# ELM327-based_OBD-II_interface.net
KiCad netlist of a schematic drawn in EAGLE
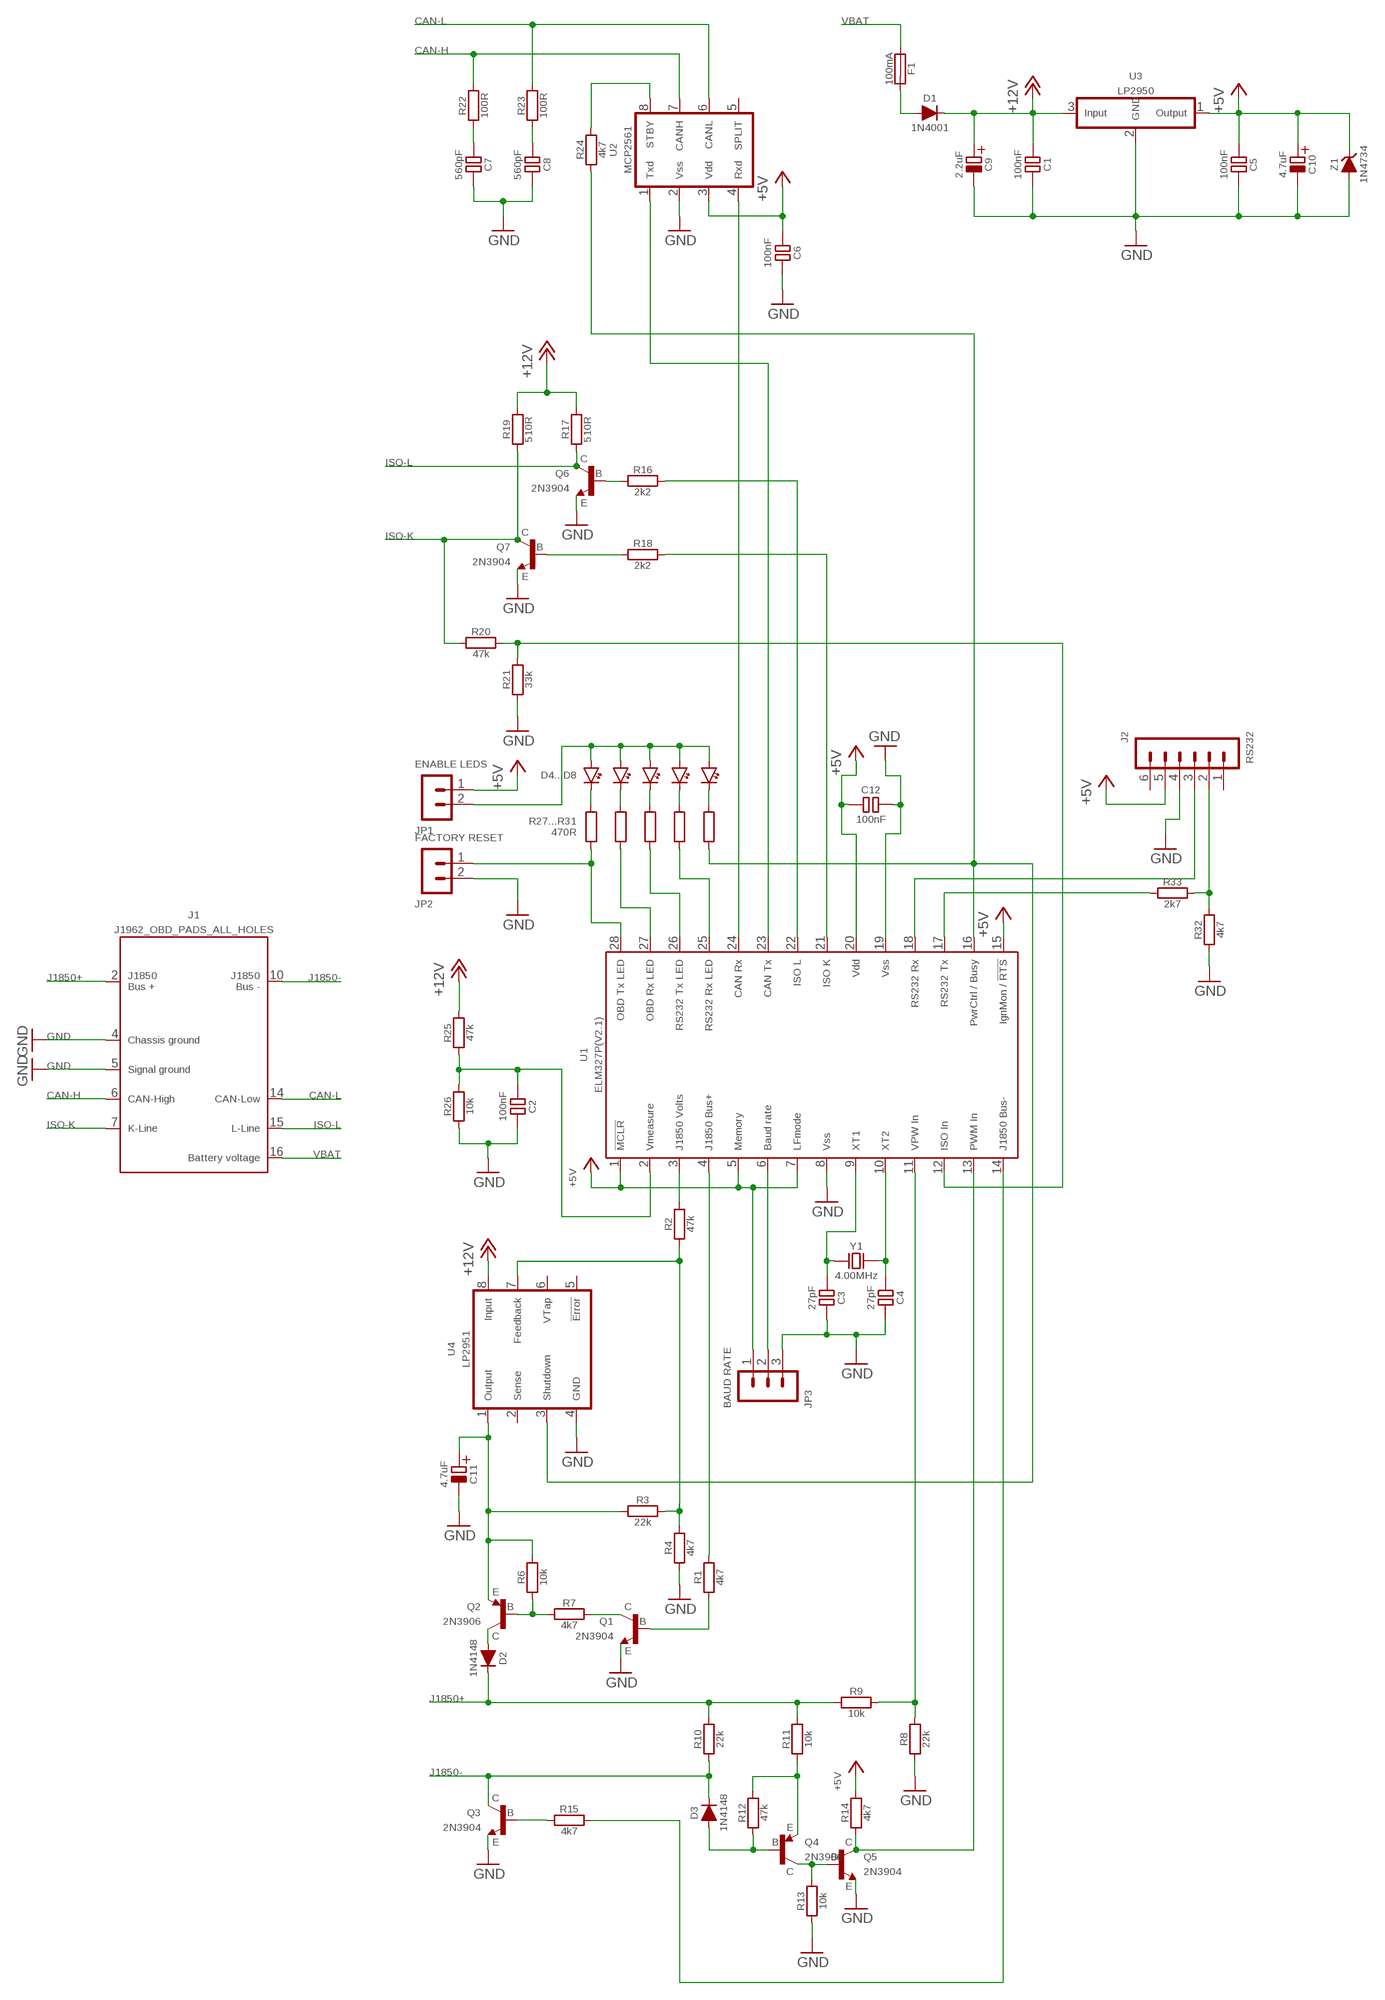
[diagram p0: schematic, sheet 1]

(export (version "E")
  (design (tool "Eeschema 10.0.6"))
  (components
    (comp (ref "C1")
      (value "100nF")
      (footprint "eagle-import:MLCC-5.08")
      (libsource (lib "eagle-import") (part "C(MLCC-5.08)"))
    )
    (comp (ref "C2")
      (value "100nF")
      (footprint "eagle-import:MLCC-5.08")
      (libsource (lib "eagle-import") (part "C(MLCC-5.08)"))
    )
    (comp (ref "C3")
      (value "27pF")
      (footprint "eagle-import:MLCC-5.08")
      (libsource (lib "eagle-import") (part "C(MLCC-5.08)"))
    )
    (comp (ref "C4")
      (value "27pF")
      (footprint "eagle-import:MLCC-5.08")
      (libsource (lib "eagle-import") (part "C(MLCC-5.08)"))
    )
    (comp (ref "C5")
      (value "100nF")
      (footprint "eagle-import:MLCC-5.08")
      (libsource (lib "eagle-import") (part "C(MLCC-5.08)"))
    )
    (comp (ref "C6")
      (value "100nF")
      (footprint "eagle-import:MLCC-5.08")
      (libsource (lib "eagle-import") (part "C(MLCC-5.08)"))
    )
    (comp (ref "C7")
      (value "560pF")
      (footprint "eagle-import:MLCC-5.08")
      (libsource (lib "eagle-import") (part "C(MLCC-5.08)"))
    )
    (comp (ref "C8")
      (value "560pF")
      (footprint "eagle-import:MLCC-5.08")
      (libsource (lib "eagle-import") (part "C(MLCC-5.08)"))
    )
    (comp (ref "C9")
      (value "2.2uF")
      (footprint "eagle-import:E2-5")
      (libsource (lib "eagle-import") (part "CPOL(E2-5)"))
    )
    (comp (ref "C10")
      (value "4.7uF")
      (footprint "eagle-import:TANTALUM-5.08")
      (libsource (lib "eagle-import") (part "CPOL(TANTALUM-5.08)"))
    )
    (comp (ref "C11")
      (value "4.7uF")
      (footprint "eagle-import:TANTALUM-5.08")
      (libsource (lib "eagle-import") (part "CPOL(TANTALUM-5.08)"))
    )
    (comp (ref "C12")
      (value "100nF")
      (footprint "eagle-import:MLCC-5.08")
      (libsource (lib "eagle-import") (part "C(MLCC-5.08)"))
    )
    (comp (ref "D1")
      (value "1N4001")
      (footprint "eagle-import:DO-41")
      (libsource (lib "eagle-import") (part "DIODE(?)DO-41"))
    )
    (comp (ref "D2")
      (value "1N4148")
      (footprint "eagle-import:DO-35")
      (libsource (lib "eagle-import") (part "DIODE(?)DO-35"))
    )
    (comp (ref "D3")
      (value "1N4148")
      (footprint "eagle-import:DO-35")
      (libsource (lib "eagle-import") (part "DIODE(?)DO-35"))
    )
    (comp (ref "D4")
      (value "OBD Tx")
      (footprint "eagle-import:LED_5MM")
      (libsource (lib "eagle-import") (part "LED(?)5MM"))
    )
    (comp (ref "D5")
      (value "OBD Rx")
      (footprint "eagle-import:LED_5MM")
      (libsource (lib "eagle-import") (part "LED(?)5MM"))
    )
    (comp (ref "D6")
      (value "RS232 Tx")
      (footprint "eagle-import:LED_5MM")
      (libsource (lib "eagle-import") (part "LED(?)5MM"))
    )
    (comp (ref "D7")
      (value "RS232 Rx")
      (footprint "eagle-import:LED_5MM")
      (libsource (lib "eagle-import") (part "LED(?)5MM"))
    )
    (comp (ref "D8")
      (value "ON")
      (footprint "eagle-import:LED_5MM")
      (libsource (lib "eagle-import") (part "LED(?)5MM"))
    )
    (comp (ref "F1")
      (value "100mA")
      (footprint "eagle-import:FUSE")
      (libsource (lib "eagle-import") (part "FUSE"))
    )
    (comp (ref "J1")
      (value "J1962_OBD_PADS_ALL_HOLES")
      (footprint "eagle-import:J1962_OBD_PADS_ALL_HOLES")
      (libsource (lib "eagle-import") (part "J1962_OBD_PADS_?ALL_HOLES"))
    )
    (comp (ref "J2")
      (value "RS232")
      (footprint "eagle-import:HEADER_1X6")
      (libsource (lib "eagle-import") (part "HEADER_1X6"))
    )
    (comp (ref "JP1")
      (value "ENABLE LEDS")
      (footprint "eagle-import:HEADER_1X2")
      (libsource (lib "eagle-import") (part "HEADER_1X2"))
    )
    (comp (ref "JP2")
      (value "FACTORY RESET")
      (footprint "eagle-import:HEADER_1X2")
      (libsource (lib "eagle-import") (part "HEADER_1X2"))
    )
    (comp (ref "JP3")
      (value "BAUD RATE")
      (footprint "eagle-import:HEADER_1X3")
      (libsource (lib "eagle-import") (part "HEADER_1X3"))
    )
    (comp (ref "Q1")
      (value "2N3904")
      (footprint "eagle-import:TO-92")
      (libsource (lib "eagle-import") (part "NPN(TO-92)"))
    )
    (comp (ref "Q2")
      (value "2N3906")
      (footprint "eagle-import:TO-92")
      (libsource (lib "eagle-import") (part "PNP(TO-92)"))
    )
    (comp (ref "Q3")
      (value "2N3904")
      (footprint "eagle-import:TO-92")
      (libsource (lib "eagle-import") (part "NPN(TO-92)"))
    )
    (comp (ref "Q4")
      (value "2N3906")
      (footprint "eagle-import:TO-92")
      (libsource (lib "eagle-import") (part "PNP(TO-92)"))
    )
    (comp (ref "Q5")
      (value "2N3904")
      (footprint "eagle-import:TO-92")
      (libsource (lib "eagle-import") (part "NPN(TO-92)"))
    )
    (comp (ref "Q6")
      (value "2N3904")
      (footprint "eagle-import:TO-92")
      (libsource (lib "eagle-import") (part "NPN(TO-92)"))
    )
    (comp (ref "Q7")
      (value "2N3904")
      (footprint "eagle-import:TO-92")
      (libsource (lib "eagle-import") (part "NPN(TO-92)"))
    )
    (comp (ref "R1")
      (value "4k7")
      (footprint "eagle-import:MF12-1_8W")
      (libsource (lib "eagle-import") (part "R-EU-?MF12-1/8W"))
    )
    (comp (ref "R2")
      (value "47k")
      (footprint "eagle-import:MF12-1_8W")
      (libsource (lib "eagle-import") (part "R-EU-?MF12-1/8W"))
    )
    (comp (ref "R3")
      (value "22k")
      (footprint "eagle-import:MF12-1_8W")
      (libsource (lib "eagle-import") (part "R-EU-?MF12-1/8W"))
    )
    (comp (ref "R4")
      (value "4k7")
      (footprint "eagle-import:MF12-1_8W")
      (libsource (lib "eagle-import") (part "R-EU-?MF12-1/8W"))
    )
    (comp (ref "R6")
      (value "10k")
      (footprint "eagle-import:MF12-1_8W")
      (libsource (lib "eagle-import") (part "R-EU-?MF12-1/8W"))
    )
    (comp (ref "R7")
      (value "4k7")
      (footprint "eagle-import:MF12-1_8W")
      (libsource (lib "eagle-import") (part "R-EU-?MF12-1/8W"))
    )
    (comp (ref "R8")
      (value "22k")
      (footprint "eagle-import:MF12-1_8W")
      (libsource (lib "eagle-import") (part "R-EU-?MF12-1/8W"))
    )
    (comp (ref "R9")
      (value "10k")
      (footprint "eagle-import:MF12-1_8W")
      (libsource (lib "eagle-import") (part "R-EU-?MF12-1/8W"))
    )
    (comp (ref "R10")
      (value "22k")
      (footprint "eagle-import:MF12-1_8W")
      (libsource (lib "eagle-import") (part "R-EU-?MF12-1/8W"))
    )
    (comp (ref "R11")
      (value "10k")
      (footprint "eagle-import:MF12-1_8W")
      (libsource (lib "eagle-import") (part "R-EU-?MF12-1/8W"))
    )
    (comp (ref "R12")
      (value "47k")
      (footprint "eagle-import:MF12-1_8W")
      (libsource (lib "eagle-import") (part "R-EU-?MF12-1/8W"))
    )
    (comp (ref "R13")
      (value "10k")
      (footprint "eagle-import:MF12-1_8W")
      (libsource (lib "eagle-import") (part "R-EU-?MF12-1/8W"))
    )
    (comp (ref "R14")
      (value "4k7")
      (footprint "eagle-import:MF12-1_8W")
      (libsource (lib "eagle-import") (part "R-EU-?MF12-1/8W"))
    )
    (comp (ref "R15")
      (value "4k7")
      (footprint "eagle-import:MF12-1_8W")
      (libsource (lib "eagle-import") (part "R-EU-?MF12-1/8W"))
    )
    (comp (ref "R16")
      (value "2k2")
      (footprint "eagle-import:MF12-1_8W")
      (libsource (lib "eagle-import") (part "R-EU-?MF12-1/8W"))
    )
    (comp (ref "R17")
      (value "510R")
      (footprint "eagle-import:MF50-1_2W")
      (libsource (lib "eagle-import") (part "R-EU-?MF50-1/2W"))
    )
    (comp (ref "R18")
      (value "2k2")
      (footprint "eagle-import:MF12-1_8W")
      (libsource (lib "eagle-import") (part "R-EU-?MF12-1/8W"))
    )
    (comp (ref "R19")
      (value "510R")
      (footprint "eagle-import:MF50-1_2W")
      (libsource (lib "eagle-import") (part "R-EU-?MF50-1/2W"))
    )
    (comp (ref "R20")
      (value "47k")
      (footprint "eagle-import:MF12-1_8W")
      (libsource (lib "eagle-import") (part "R-EU-?MF12-1/8W"))
    )
    (comp (ref "R21")
      (value "33k")
      (footprint "eagle-import:MF12-1_8W")
      (libsource (lib "eagle-import") (part "R-EU-?MF12-1/8W"))
    )
    (comp (ref "R22")
      (value "100R")
      (footprint "eagle-import:MF12-1_8W")
      (libsource (lib "eagle-import") (part "R-EU-?MF12-1/8W"))
    )
    (comp (ref "R23")
      (value "100R")
      (footprint "eagle-import:MF12-1_8W")
      (libsource (lib "eagle-import") (part "R-EU-?MF12-1/8W"))
    )
    (comp (ref "R24")
      (value "4k7")
      (footprint "eagle-import:MF12-1_8W")
      (libsource (lib "eagle-import") (part "R-EU-?MF12-1/8W"))
    )
    (comp (ref "R25")
      (value "47k")
      (footprint "eagle-import:MF12-1_8W")
      (libsource (lib "eagle-import") (part "R-EU-?MF12-1/8W"))
    )
    (comp (ref "R26")
      (value "10k")
      (footprint "eagle-import:MF12-1_8W")
      (libsource (lib "eagle-import") (part "R-EU-?MF12-1/8W"))
    )
    (comp (ref "R27")
      (value "470R")
      (footprint "eagle-import:MF12-1_8W")
      (libsource (lib "eagle-import") (part "R-EU-?MF12-1/8W"))
    )
    (comp (ref "R28")
      (value "470R")
      (footprint "eagle-import:MF12-1_8W")
      (libsource (lib "eagle-import") (part "R-EU-?MF12-1/8W"))
    )
    (comp (ref "R29")
      (value "470R")
      (footprint "eagle-import:MF12-1_8W")
      (libsource (lib "eagle-import") (part "R-EU-?MF12-1/8W"))
    )
    (comp (ref "R30")
      (value "470R")
      (footprint "eagle-import:MF12-1_8W")
      (libsource (lib "eagle-import") (part "R-EU-?MF12-1/8W"))
    )
    (comp (ref "R31")
      (value "470R")
      (footprint "eagle-import:MF12-1_8W")
      (libsource (lib "eagle-import") (part "R-EU-?MF12-1/8W"))
    )
    (comp (ref "R32")
      (value "4k7")
      (footprint "eagle-import:MF12-1_8W")
      (libsource (lib "eagle-import") (part "R-EU-?MF12-1/8W"))
    )
    (comp (ref "R33")
      (value "2k7")
      (footprint "eagle-import:MF12-1_8W")
      (libsource (lib "eagle-import") (part "R-EU-?MF12-1/8W"))
    )
    (comp (ref "U1")
      (value "ELM327P(V2.1)")
      (footprint "eagle-import:SPDIP(28)")
      (libsource (lib "eagle-import") (part "ELM327?(V2.1)P"))
    )
    (comp (ref "U2")
      (value "MCP2561")
      (footprint "eagle-import:PDIP")
      (libsource (lib "eagle-import") (part "MCP2561FD(?)PDIP"))
    )
    (comp (ref "U3")
      (value "LP2950")
      (footprint "eagle-import:TO-92")
      (libsource (lib "eagle-import") (part "LP2950?Z-5.0AC"))
    )
    (comp (ref "U4")
      (value "LP2951")
      (footprint "eagle-import:PDIP-8")
      (libsource (lib "eagle-import") (part "LP2951?NAC"))
    )
    (comp (ref "Y1")
      (value "4.00MHz")
      (footprint "eagle-import:HC49")
      (libsource (lib "eagle-import") (part "HUS-4.000-18-30/50/-40+85"))
    )
    (comp (ref "Z1")
      (value "1N4734")
      (footprint "eagle-import:DO-41")
      (libsource (lib "eagle-import") (part "ZENER(?)DO-41"))
    )
  )
  (nets
    (net (code "1") (name "+5V") (class "Default")
      (node (ref "C10") (pin "+") (pinfunction "+_+") (pintype "passive"))
      (node (ref "C12") (pin "+") (pinfunction "+_+") (pintype "passive"))
      (node (ref "C5") (pin "+") (pinfunction "+_+") (pintype "passive"))
      (node (ref "C6") (pin "+") (pinfunction "+_+") (pintype "passive"))
      (node (ref "J2") (pin "5") (pinfunction "5_5") (pintype "passive"))
      (node (ref "JP1") (pin "1") (pinfunction "1_1") (pintype "passive"))
      (node (ref "JP3") (pin "1") (pinfunction "1_1") (pintype "passive"))
      (node (ref "R14") (pin "2") (pinfunction "2_2") (pintype "passive"))
      (node (ref "U1") (pin "1") (pinfunction "~{MCLR}_1") (pintype "input"))
      (node (ref "U1") (pin "15") (pinfunction "IGNMON/~{RTS}_15") (pintype "bidirectional"))
      (node (ref "U1") (pin "20") (pinfunction "VDD_20") (pintype "bidirectional"))
      (node (ref "U1") (pin "5") (pinfunction "MEMORY_5") (pintype "bidirectional"))
      (node (ref "U1") (pin "7") (pinfunction "LFMODE_7") (pintype "bidirectional"))
      (node (ref "U2") (pin "3") (pinfunction "VDD_3") (pintype "bidirectional"))
      (node (ref "U3") (pin "1") (pinfunction "OUTPUT_1") (pintype "bidirectional"))
      (node (ref "Z1") (pin "C") (pinfunction "C_C") (pintype "passive"))
    )
    (net (code "2") (name "+12V") (class "Default")
      (node (ref "C1") (pin "+") (pinfunction "+_+") (pintype "passive"))
      (node (ref "C9") (pin "+") (pinfunction "+_+") (pintype "passive"))
      (node (ref "D1") (pin "C") (pinfunction "C_C") (pintype "passive"))
      (node (ref "R17") (pin "2") (pinfunction "2_2") (pintype "passive"))
      (node (ref "R19") (pin "2") (pinfunction "2_2") (pintype "passive"))
      (node (ref "R25") (pin "2") (pinfunction "2_2") (pintype "passive"))
      (node (ref "U3") (pin "3") (pinfunction "INPUT_3") (pintype "bidirectional"))
      (node (ref "U4") (pin "8") (pinfunction "INPUT_8") (pintype "bidirectional"))
    )
    (net (code "3") (name "/CAN-H") (class "Default")
      (node (ref "J1") (pin "6") (pinfunction "6_6") (pintype "bidirectional"))
      (node (ref "R22") (pin "2") (pinfunction "2_2") (pintype "passive"))
      (node (ref "U2") (pin "7") (pinfunction "CANH_7") (pintype "bidirectional"))
    )
    (net (code "4") (name "/CAN-L") (class "Default")
      (node (ref "J1") (pin "14") (pinfunction "14_14") (pintype "bidirectional"))
      (node (ref "R23") (pin "2") (pinfunction "2_2") (pintype "passive"))
      (node (ref "U2") (pin "6") (pinfunction "CANL_6") (pintype "bidirectional"))
    )
    (net (code "5") (name "/ISO-K") (class "Default")
      (node (ref "J1") (pin "7") (pinfunction "7_7") (pintype "bidirectional"))
      (node (ref "Q7") (pin "C") (pinfunction "C_C") (pintype "passive"))
      (node (ref "R19") (pin "1") (pinfunction "1_1") (pintype "passive"))
      (node (ref "R20") (pin "1") (pinfunction "1_1") (pintype "passive"))
    )
    (net (code "6") (name "/ISO-L") (class "Default")
      (node (ref "J1") (pin "15") (pinfunction "15_15") (pintype "bidirectional"))
      (node (ref "Q6") (pin "C") (pinfunction "C_C") (pintype "passive"))
      (node (ref "R17") (pin "1") (pinfunction "1_1") (pintype "passive"))
    )
    (net (code "7") (name "/J1850+") (class "Default")
      (node (ref "D2") (pin "C") (pinfunction "C_C") (pintype "passive"))
      (node (ref "J1") (pin "2") (pinfunction "2_2") (pintype "bidirectional"))
      (node (ref "R10") (pin "2") (pinfunction "2_2") (pintype "passive"))
      (node (ref "R11") (pin "2") (pinfunction "2_2") (pintype "passive"))
      (node (ref "R9") (pin "1") (pinfunction "1_1") (pintype "passive"))
    )
    (net (code "8") (name "/J1850-") (class "Default")
      (node (ref "D3") (pin "C") (pinfunction "C_C") (pintype "passive"))
      (node (ref "J1") (pin "10") (pinfunction "10_10") (pintype "bidirectional"))
      (node (ref "Q3") (pin "C") (pinfunction "C_C") (pintype "passive"))
      (node (ref "R10") (pin "1") (pinfunction "1_1") (pintype "passive"))
    )
    (net (code "9") (name "/VBAT") (class "Default")
      (node (ref "F1") (pin "1") (pinfunction "1_1") (pintype "passive"))
      (node (ref "J1") (pin "16") (pinfunction "16_16") (pintype "bidirectional"))
    )
    (net (code "10") (name "GND") (class "Default")
      (node (ref "C1") (pin "-") (pinfunction "-_-") (pintype "passive"))
      (node (ref "C10") (pin "-") (pinfunction "-_-") (pintype "passive"))
      (node (ref "C11") (pin "-") (pinfunction "-_-") (pintype "passive"))
      (node (ref "C12") (pin "-") (pinfunction "-_-") (pintype "passive"))
      (node (ref "C2") (pin "-") (pinfunction "-_-") (pintype "passive"))
      (node (ref "C3") (pin "-") (pinfunction "-_-") (pintype "passive"))
      (node (ref "C4") (pin "-") (pinfunction "-_-") (pintype "passive"))
      (node (ref "C5") (pin "-") (pinfunction "-_-") (pintype "passive"))
      (node (ref "C6") (pin "-") (pinfunction "-_-") (pintype "passive"))
      (node (ref "C7") (pin "-") (pinfunction "-_-") (pintype "passive"))
      (node (ref "C8") (pin "-") (pinfunction "-_-") (pintype "passive"))
      (node (ref "C9") (pin "-") (pinfunction "-_-") (pintype "passive"))
      (node (ref "J1") (pin "4") (pinfunction "4_4") (pintype "bidirectional"))
      (node (ref "J1") (pin "5") (pinfunction "5_5") (pintype "bidirectional"))
      (node (ref "J2") (pin "4") (pinfunction "4_4") (pintype "passive"))
      (node (ref "JP2") (pin "2") (pinfunction "2_2") (pintype "passive"))
      (node (ref "JP3") (pin "3") (pinfunction "3_3") (pintype "passive"))
      (node (ref "Q1") (pin "E") (pinfunction "E_E") (pintype "passive"))
      (node (ref "Q3") (pin "E") (pinfunction "E_E") (pintype "passive"))
      (node (ref "Q5") (pin "E") (pinfunction "E_E") (pintype "passive"))
      (node (ref "Q6") (pin "E") (pinfunction "E_E") (pintype "passive"))
      (node (ref "Q7") (pin "E") (pinfunction "E_E") (pintype "passive"))
      (node (ref "R13") (pin "1") (pinfunction "1_1") (pintype "passive"))
      (node (ref "R21") (pin "1") (pinfunction "1_1") (pintype "passive"))
      (node (ref "R26") (pin "1") (pinfunction "1_1") (pintype "passive"))
      (node (ref "R32") (pin "1") (pinfunction "1_1") (pintype "passive"))
      (node (ref "R4") (pin "1") (pinfunction "1_1") (pintype "passive"))
      (node (ref "R8") (pin "1") (pinfunction "1_1") (pintype "passive"))
      (node (ref "U1") (pin "19") (pinfunction "VSS_19") (pintype "bidirectional"))
      (node (ref "U1") (pin "8") (pinfunction "VSS_8") (pintype "bidirectional"))
      (node (ref "U2") (pin "2") (pinfunction "VSS_2") (pintype "bidirectional"))
      (node (ref "U3") (pin "2") (pinfunction "GND_2") (pintype "bidirectional"))
      (node (ref "U4") (pin "4") (pinfunction "GND_4") (pintype "bidirectional"))
      (node (ref "Z1") (pin "A") (pinfunction "A_A") (pintype "passive"))
    )
    (net (code "11") (name "Net-(C7-Pad+)") (class "Default")
      (node (ref "C7") (pin "+") (pinfunction "+_+") (pintype "passive"))
      (node (ref "R22") (pin "1") (pinfunction "1_1") (pintype "passive"))
    )
    (net (code "12") (name "Net-(C8-Pad+)") (class "Default")
      (node (ref "C8") (pin "+") (pinfunction "+_+") (pintype "passive"))
      (node (ref "R23") (pin "1") (pinfunction "1_1") (pintype "passive"))
    )
    (net (code "13") (name "Net-(D1-PadA)") (class "Default")
      (node (ref "D1") (pin "A") (pinfunction "A_A") (pintype "passive"))
      (node (ref "F1") (pin "2") (pinfunction "2_2") (pintype "passive"))
    )
    (net (code "14") (name "Net-(D2-PadA)") (class "Default")
      (node (ref "D2") (pin "A") (pinfunction "A_A") (pintype "passive"))
      (node (ref "Q2") (pin "C") (pinfunction "C_C") (pintype "passive"))
    )
    (net (code "15") (name "Net-(D3-PadA)") (class "Default")
      (node (ref "D3") (pin "A") (pinfunction "A_A") (pintype "passive"))
      (node (ref "Q4") (pin "B") (pinfunction "B_B") (pintype "passive"))
      (node (ref "R12") (pin "1") (pinfunction "1_1") (pintype "passive"))
    )
    (net (code "16") (name "Net-(D4-PadA)") (class "Default")
      (node (ref "D4") (pin "A") (pinfunction "A_A") (pintype "passive"))
      (node (ref "D5") (pin "A") (pinfunction "A_A") (pintype "passive"))
      (node (ref "D6") (pin "A") (pinfunction "A_A") (pintype "passive"))
      (node (ref "D7") (pin "A") (pinfunction "A_A") (pintype "passive"))
      (node (ref "D8") (pin "A") (pinfunction "A_A") (pintype "passive"))
      (node (ref "JP1") (pin "2") (pinfunction "2_2") (pintype "passive"))
    )
    (net (code "17") (name "Net-(D4-PadC)") (class "Default")
      (node (ref "D4") (pin "C") (pinfunction "C_C") (pintype "passive"))
      (node (ref "R27") (pin "2") (pinfunction "2_2") (pintype "passive"))
    )
    (net (code "18") (name "Net-(D5-PadC)") (class "Default")
      (node (ref "D5") (pin "C") (pinfunction "C_C") (pintype "passive"))
      (node (ref "R28") (pin "2") (pinfunction "2_2") (pintype "passive"))
    )
    (net (code "19") (name "Net-(D6-PadC)") (class "Default")
      (node (ref "D6") (pin "C") (pinfunction "C_C") (pintype "passive"))
      (node (ref "R29") (pin "2") (pinfunction "2_2") (pintype "passive"))
    )
    (net (code "20") (name "Net-(D7-PadC)") (class "Default")
      (node (ref "D7") (pin "C") (pinfunction "C_C") (pintype "passive"))
      (node (ref "R30") (pin "2") (pinfunction "2_2") (pintype "passive"))
    )
    (net (code "21") (name "Net-(D8-PadC)") (class "Default")
      (node (ref "D8") (pin "C") (pinfunction "C_C") (pintype "passive"))
      (node (ref "R31") (pin "2") (pinfunction "2_2") (pintype "passive"))
    )
    (net (code "22") (name "Net-(J2-Pad2)") (class "Default")
      (node (ref "J2") (pin "2") (pinfunction "2_2") (pintype "passive"))
      (node (ref "R32") (pin "2") (pinfunction "2_2") (pintype "passive"))
      (node (ref "R33") (pin "2") (pinfunction "2_2") (pintype "passive"))
    )
    (net (code "23") (name "Net-(Q1-PadB)") (class "Default")
      (node (ref "Q1") (pin "B") (pinfunction "B_B") (pintype "passive"))
      (node (ref "R1") (pin "1") (pinfunction "1_1") (pintype "passive"))
    )
    (net (code "24") (name "Net-(Q1-PadC)") (class "Default")
      (node (ref "Q1") (pin "C") (pinfunction "C_C") (pintype "passive"))
      (node (ref "R7") (pin "2") (pinfunction "2_2") (pintype "passive"))
    )
    (net (code "25") (name "Net-(Q2-PadB)") (class "Default")
      (node (ref "Q2") (pin "B") (pinfunction "B_B") (pintype "passive"))
      (node (ref "R6") (pin "1") (pinfunction "1_1") (pintype "passive"))
      (node (ref "R7") (pin "1") (pinfunction "1_1") (pintype "passive"))
    )
    (net (code "26") (name "Net-(Q3-PadB)") (class "Default")
      (node (ref "Q3") (pin "B") (pinfunction "B_B") (pintype "passive"))
      (node (ref "R15") (pin "1") (pinfunction "1_1") (pintype "passive"))
    )
    (net (code "27") (name "Net-(Q4-PadC)") (class "Default")
      (node (ref "Q4") (pin "C") (pinfunction "C_C") (pintype "passive"))
      (node (ref "Q5") (pin "B") (pinfunction "B_B") (pintype "passive"))
      (node (ref "R13") (pin "2") (pinfunction "2_2") (pintype "passive"))
    )
    (net (code "28") (name "Net-(Q4-PadE)") (class "Default")
      (node (ref "Q4") (pin "E") (pinfunction "E_E") (pintype "passive"))
      (node (ref "R11") (pin "1") (pinfunction "1_1") (pintype "passive"))
      (node (ref "R12") (pin "2") (pinfunction "2_2") (pintype "passive"))
    )
    (net (code "29") (name "Net-(Q6-PadB)") (class "Default")
      (node (ref "Q6") (pin "B") (pinfunction "B_B") (pintype "passive"))
      (node (ref "R16") (pin "1") (pinfunction "1_1") (pintype "passive"))
    )
    (net (code "30") (name "Net-(Q7-PadB)") (class "Default")
      (node (ref "Q7") (pin "B") (pinfunction "B_B") (pintype "passive"))
      (node (ref "R18") (pin "1") (pinfunction "1_1") (pintype "passive"))
    )
    (net (code "31") (name "Net-(U1-BAUD_RATE)") (class "Default")
      (node (ref "JP3") (pin "2") (pinfunction "2_2") (pintype "passive"))
      (node (ref "U1") (pin "6") (pinfunction "BAUD_RATE_6") (pintype "bidirectional"))
    )
    (net (code "32") (name "Net-(U1-CAN_RX)") (class "Default")
      (node (ref "U1") (pin "24") (pinfunction "CAN_RX_24") (pintype "bidirectional"))
      (node (ref "U2") (pin "4") (pinfunction "RXD_4") (pintype "bidirectional"))
    )
    (net (code "33") (name "Net-(U1-CAN_TX)") (class "Default")
      (node (ref "U1") (pin "23") (pinfunction "CAN_TX_23") (pintype "bidirectional"))
      (node (ref "U2") (pin "1") (pinfunction "TXD_1") (pintype "bidirectional"))
    )
    (net (code "34") (name "Net-(U1-ISO_IN)") (class "Default")
      (node (ref "R20") (pin "2") (pinfunction "2_2") (pintype "passive"))
      (node (ref "R21") (pin "2") (pinfunction "2_2") (pintype "passive"))
      (node (ref "U1") (pin "12") (pinfunction "ISO_IN_12") (pintype "bidirectional"))
    )
    (net (code "35") (name "Net-(U1-ISO_K)") (class "Default")
      (node (ref "R18") (pin "2") (pinfunction "2_2") (pintype "passive"))
      (node (ref "U1") (pin "21") (pinfunction "ISO_K_21") (pintype "bidirectional"))
    )
    (net (code "36") (name "Net-(U1-ISO_L)") (class "Default")
      (node (ref "R16") (pin "2") (pinfunction "2_2") (pintype "passive"))
      (node (ref "U1") (pin "22") (pinfunction "ISO_L_22") (pintype "bidirectional"))
    )
    (net (code "37") (name "Net-(U1-J1850_BUS+)") (class "Default")
      (node (ref "R1") (pin "2") (pinfunction "2_2") (pintype "passive"))
      (node (ref "U1") (pin "4") (pinfunction "J1850_BUS+_4") (pintype "bidirectional"))
    )
    (net (code "38") (name "Net-(U1-J1850_BUS-)") (class "Default")
      (node (ref "R15") (pin "2") (pinfunction "2_2") (pintype "passive"))
      (node (ref "U1") (pin "14") (pinfunction "J1850_BUS-_14") (pintype "bidirectional"))
    )
    (net (code "39") (name "Net-(U1-J1850_VOLTS)") (class "Default")
      (node (ref "R2") (pin "2") (pinfunction "2_2") (pintype "passive"))
      (node (ref "U1") (pin "3") (pinfunction "J1850_VOLTS_3") (pintype "bidirectional"))
    )
    (net (code "40") (name "Net-(U1-OBD_RX_LED)") (class "Default")
      (node (ref "R28") (pin "1") (pinfunction "1_1") (pintype "passive"))
      (node (ref "U1") (pin "27") (pinfunction "OBD_RX_LED_27") (pintype "bidirectional"))
    )
    (net (code "41") (name "Net-(U1-OBD_TX_LED)") (class "Default")
      (node (ref "JP2") (pin "1") (pinfunction "1_1") (pintype "passive"))
      (node (ref "R27") (pin "1") (pinfunction "1_1") (pintype "passive"))
      (node (ref "U1") (pin "28") (pinfunction "OBD_TX_LED_28") (pintype "bidirectional"))
    )
    (net (code "42") (name "Net-(U1-PWM_IN)") (class "Default")
      (node (ref "Q5") (pin "C") (pinfunction "C_C") (pintype "passive"))
      (node (ref "R14") (pin "1") (pinfunction "1_1") (pintype "passive"))
      (node (ref "U1") (pin "13") (pinfunction "PWM_IN_13") (pintype "bidirectional"))
    )
    (net (code "43") (name "Net-(U1-PWRCTRL{slash}BUSY)") (class "Default")
      (node (ref "R24") (pin "1") (pinfunction "1_1") (pintype "passive"))
      (node (ref "R31") (pin "1") (pinfunction "1_1") (pintype "passive"))
      (node (ref "U1") (pin "16") (pinfunction "PWRCTRL/BUSY_16") (pintype "bidirectional"))
      (node (ref "U4") (pin "3") (pinfunction "SHUTDOWN_3") (pintype "bidirectional"))
    )
    (net (code "44") (name "Net-(U1-RS232_RX)") (class "Default")
      (node (ref "J2") (pin "3") (pinfunction "3_3") (pintype "passive"))
      (node (ref "U1") (pin "18") (pinfunction "RS232_RX_18") (pintype "bidirectional"))
    )
    (net (code "45") (name "Net-(U1-RS232_RX_LED)") (class "Default")
      (node (ref "R30") (pin "1") (pinfunction "1_1") (pintype "passive"))
      (node (ref "U1") (pin "25") (pinfunction "RS232_RX_LED_25") (pintype "bidirectional"))
    )
    (net (code "46") (name "Net-(U1-RS232_TX)") (class "Default")
      (node (ref "R33") (pin "1") (pinfunction "1_1") (pintype "passive"))
      (node (ref "U1") (pin "17") (pinfunction "RS232_TX_17") (pintype "bidirectional"))
    )
    (net (code "47") (name "Net-(U1-RS232_TX_LED)") (class "Default")
      (node (ref "R29") (pin "1") (pinfunction "1_1") (pintype "passive"))
      (node (ref "U1") (pin "26") (pinfunction "RS232_TX_LED_26") (pintype "bidirectional"))
    )
    (net (code "48") (name "Net-(U1-VMEASURE)") (class "Default")
      (node (ref "C2") (pin "+") (pinfunction "+_+") (pintype "passive"))
      (node (ref "R25") (pin "1") (pinfunction "1_1") (pintype "passive"))
      (node (ref "R26") (pin "2") (pinfunction "2_2") (pintype "passive"))
      (node (ref "U1") (pin "2") (pinfunction "VMEASURE_2") (pintype "bidirectional"))
    )
    (net (code "49") (name "Net-(U1-VPW_IN)") (class "Default")
      (node (ref "R8") (pin "2") (pinfunction "2_2") (pintype "passive"))
      (node (ref "R9") (pin "2") (pinfunction "2_2") (pintype "passive"))
      (node (ref "U1") (pin "11") (pinfunction "VPW_IN_11") (pintype "bidirectional"))
    )
    (net (code "50") (name "Net-(U1-XT1)") (class "Default")
      (node (ref "C3") (pin "+") (pinfunction "+_+") (pintype "passive"))
      (node (ref "U1") (pin "9") (pinfunction "XT1_9") (pintype "input"))
      (node (ref "Y1") (pin "1") (pinfunction "1_1") (pintype "passive"))
    )
    (net (code "51") (name "Net-(U1-XT2)") (class "Default")
      (node (ref "C4") (pin "+") (pinfunction "+_+") (pintype "passive"))
      (node (ref "U1") (pin "10") (pinfunction "XT2_10") (pintype "bidirectional"))
      (node (ref "Y1") (pin "2") (pinfunction "2_2") (pintype "passive"))
    )
    (net (code "52") (name "Net-(U2-STBY)") (class "Default")
      (node (ref "R24") (pin "2") (pinfunction "2_2") (pintype "passive"))
      (node (ref "U2") (pin "8") (pinfunction "STBY_8") (pintype "bidirectional"))
    )
    (net (code "53") (name "Net-(U4-FEEDBACK)") (class "Default")
      (node (ref "R2") (pin "1") (pinfunction "1_1") (pintype "passive"))
      (node (ref "R3") (pin "2") (pinfunction "2_2") (pintype "passive"))
      (node (ref "R4") (pin "2") (pinfunction "2_2") (pintype "passive"))
      (node (ref "U4") (pin "7") (pinfunction "FEEDBACK_7") (pintype "bidirectional"))
    )
    (net (code "54") (name "Net-(U4-OUTPUT)") (class "Default")
      (node (ref "C11") (pin "+") (pinfunction "+_+") (pintype "passive"))
      (node (ref "Q2") (pin "E") (pinfunction "E_E") (pintype "passive"))
      (node (ref "R3") (pin "1") (pinfunction "1_1") (pintype "passive"))
      (node (ref "R6") (pin "2") (pinfunction "2_2") (pintype "passive"))
      (node (ref "U4") (pin "1") (pinfunction "OUTPUT_1") (pintype "bidirectional"))
    )
    (net (code "55") (name "unconnected-(J2-Pad1)") (class "Default")
      (node (ref "J2") (pin "1") (pinfunction "1_1") (pintype "passive"))
    )
    (net (code "56") (name "unconnected-(J2-Pad6)") (class "Default")
      (node (ref "J2") (pin "6") (pinfunction "6_6") (pintype "passive"))
    )
    (net (code "57") (name "unconnected-(U2-SPLIT-Pad5)") (class "Default")
      (node (ref "U2") (pin "5") (pinfunction "SPLIT_5") (pintype "bidirectional"))
    )
    (net (code "58") (name "unconnected-(U4-ERROROUTPUT-Pad5)") (class "Default")
      (node (ref "U4") (pin "5") (pinfunction "ERROROUTPUT_5") (pintype "bidirectional"))
    )
    (net (code "59") (name "unconnected-(U4-SENSE-Pad2)") (class "Default")
      (node (ref "U4") (pin "2") (pinfunction "SENSE_2") (pintype "bidirectional"))
    )
    (net (code "60") (name "unconnected-(U4-VOTAP-Pad6)") (class "Default")
      (node (ref "U4") (pin "6") (pinfunction "VOTAP_6") (pintype "bidirectional"))
    )
  )
)
